# RamyunActionBoard.net
KiCad netlist of a schematic drawn in EAGLE
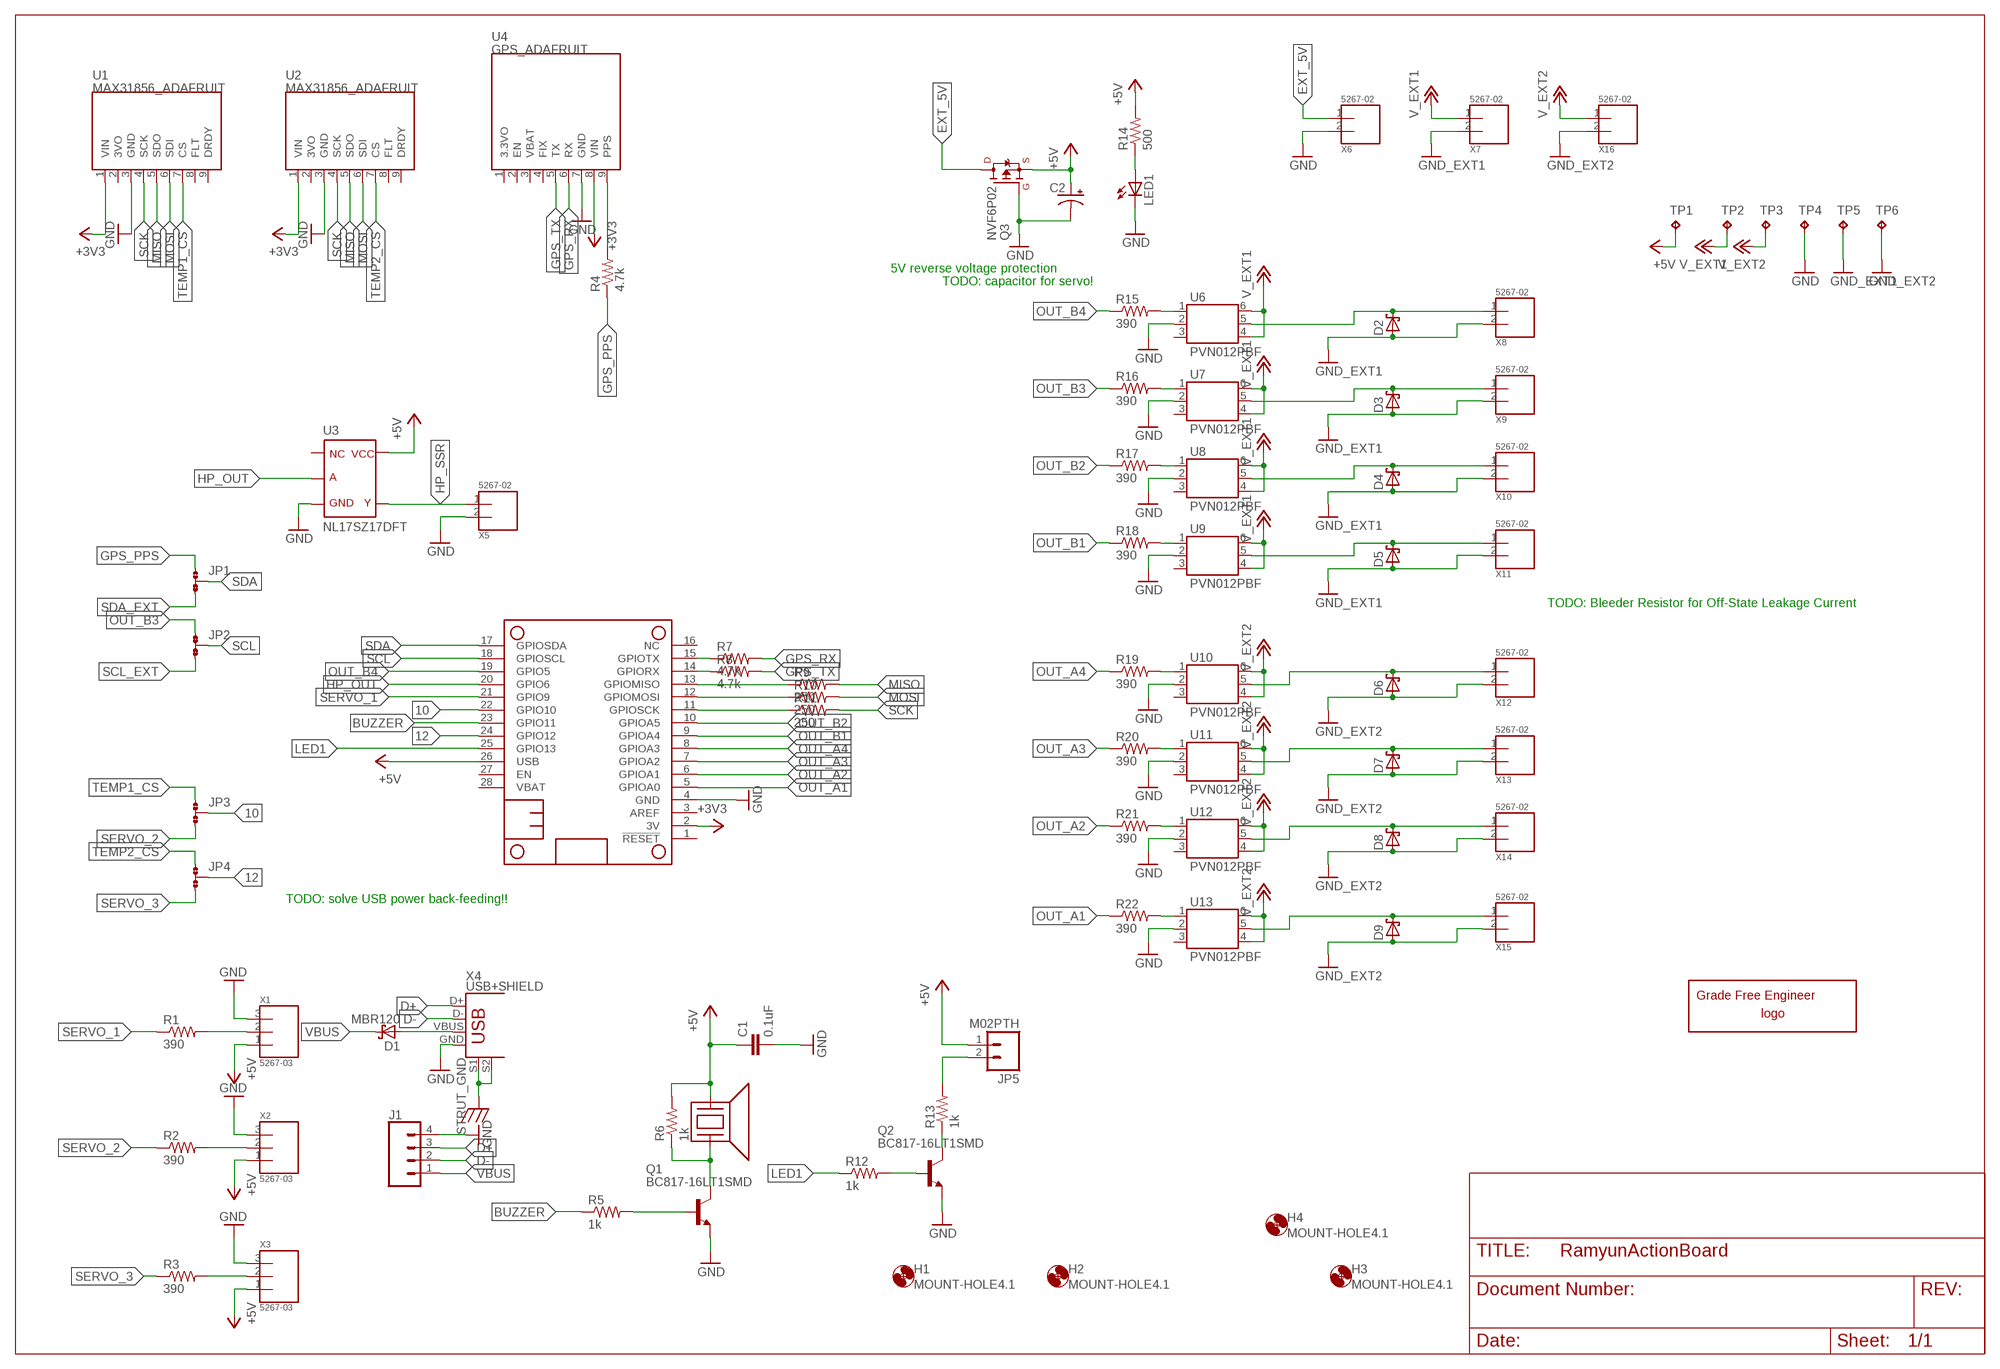
[diagram p0: schematic, sheet 1]

(export (version "E")
  (design (tool "Eeschema 10.0.6"))
  (components
    (comp (ref "C1")
      (value "0.1uF")
      (footprint "eagle-import:C0603(1608)_HANDSOLDER")
      (libsource (lib "eagle-import") (part "C0603(1608)_HAND"))
    )
    (comp (ref "C2")
      (value "CPOL-USE3.5-8")
      (footprint "eagle-import:E3,5-8")
      (libsource (lib "eagle-import") (part "CPOL-USE3.5-8"))
    )
    (comp (ref "D1")
      (value "MBR120")
      (footprint "eagle-import:SOD-123")
      (libsource (lib "eagle-import") (part "MBR120"))
    )
    (comp (ref "D2")
      (value "MBR5200VPTR-E1_V")
      (footprint "eagle-import:DO-27-VERTICAL")
      (libsource (lib "eagle-import") (part "MBR5200VPTR-E1_V"))
    )
    (comp (ref "D3")
      (value "MBR5200VPTR-E1_V")
      (footprint "eagle-import:DO-27-VERTICAL")
      (libsource (lib "eagle-import") (part "MBR5200VPTR-E1_V"))
    )
    (comp (ref "D4")
      (value "MBR5200VPTR-E1_V")
      (footprint "eagle-import:DO-27-VERTICAL")
      (libsource (lib "eagle-import") (part "MBR5200VPTR-E1_V"))
    )
    (comp (ref "D5")
      (value "MBR5200VPTR-E1_V")
      (footprint "eagle-import:DO-27-VERTICAL")
      (libsource (lib "eagle-import") (part "MBR5200VPTR-E1_V"))
    )
    (comp (ref "D6")
      (value "MBR5200VPTR-E1_V")
      (footprint "eagle-import:DO-27-VERTICAL")
      (libsource (lib "eagle-import") (part "MBR5200VPTR-E1_V"))
    )
    (comp (ref "D7")
      (value "MBR5200VPTR-E1_V")
      (footprint "eagle-import:DO-27-VERTICAL")
      (libsource (lib "eagle-import") (part "MBR5200VPTR-E1_V"))
    )
    (comp (ref "D8")
      (value "MBR5200VPTR-E1_V")
      (footprint "eagle-import:DO-27-VERTICAL")
      (libsource (lib "eagle-import") (part "MBR5200VPTR-E1_V"))
    )
    (comp (ref "D9")
      (value "MBR5200VPTR-E1_V")
      (footprint "eagle-import:DO-27-VERTICAL")
      (libsource (lib "eagle-import") (part "MBR5200VPTR-E1_V"))
    )
    (comp (ref "H1")
      (value "MOUNT-HOLE4.1")
      (footprint "eagle-import:4,1")
      (libsource (lib "eagle-import") (part "MOUNT-HOLE4.1"))
    )
    (comp (ref "H2")
      (value "MOUNT-HOLE4.1")
      (footprint "eagle-import:4,1")
      (libsource (lib "eagle-import") (part "MOUNT-HOLE4.1"))
    )
    (comp (ref "H3")
      (value "MOUNT-HOLE4.1")
      (footprint "eagle-import:4,1")
      (libsource (lib "eagle-import") (part "MOUNT-HOLE4.1"))
    )
    (comp (ref "H4")
      (value "MOUNT-HOLE4.1")
      (footprint "eagle-import:4,1")
      (libsource (lib "eagle-import") (part "MOUNT-HOLE4.1"))
    )
    (comp (ref "J1")
      (value "CONN_04")
      (footprint "eagle-import:1X04")
      (libsource (lib "eagle-import") (part "CONN_04"))
    )
    (comp (ref "JP1")
      (value "JP2")
      (footprint "eagle-import:JP2SMD0603")
      (libsource (lib "eagle-import") (part "JP2"))
    )
    (comp (ref "JP2")
      (value "JP2")
      (footprint "eagle-import:JP2SMD0603")
      (libsource (lib "eagle-import") (part "JP2"))
    )
    (comp (ref "JP3")
      (value "JP2")
      (footprint "eagle-import:JP2SMD0603")
      (libsource (lib "eagle-import") (part "JP2"))
    )
    (comp (ref "JP4")
      (value "JP2")
      (footprint "eagle-import:JP2SMD0603")
      (libsource (lib "eagle-import") (part "JP2"))
    )
    (comp (ref "JP5")
      (value "M02PTH")
      (footprint "eagle-import:1X02")
      (libsource (lib "eagle-import") (part "M02PTH"))
    )
    (comp (ref "LED1")
      (value "LED3MM")
      (footprint "eagle-import:LED3MM")
      (libsource (lib "eagle-import") (part "LED3MM"))
    )
    (comp (ref "LOGO1")
      (value "GRADEFREELOGO-20")
      (footprint "eagle-import:GRADEFREELOGO-20")
      (libsource (lib "eagle-import") (part "GRADEFREELOGO-20"))
    )
    (comp (ref "MS1")
      (value "FEATHERWING_NODIM")
      (footprint "eagle-import:FEATHERWING_DIM")
      (libsource (lib "eagle-import") (part "FEATHERWING_NODIM"))
    )
    (comp (ref "Q1")
      (value "BC817-16LT1SMD")
      (footprint "eagle-import:SOT23-BEC")
      (libsource (lib "eagle-import") (part "BC817SMD-16LT1"))
    )
    (comp (ref "Q2")
      (value "BC817-16LT1SMD")
      (footprint "eagle-import:SOT23-BEC")
      (libsource (lib "eagle-import") (part "BC817SMD-16LT1"))
    )
    (comp (ref "Q3")
      (value "NVF6P02")
      (footprint "eagle-import:SOT223")
      (libsource (lib "eagle-import") (part "NVF6P02"))
    )
    (comp (ref "R1")
      (value "390")
      (footprint "eagle-import:R0603(1608)_HANDSOLDER")
      (libsource (lib "eagle-import") (part "R0603(1608)_HAND"))
    )
    (comp (ref "R2")
      (value "390")
      (footprint "eagle-import:R0603(1608)_HANDSOLDER")
      (libsource (lib "eagle-import") (part "R0603(1608)_HAND"))
    )
    (comp (ref "R3")
      (value "390")
      (footprint "eagle-import:R0603(1608)_HANDSOLDER")
      (libsource (lib "eagle-import") (part "R0603(1608)_HAND"))
    )
    (comp (ref "R4")
      (value "4.7k")
      (footprint "eagle-import:R0603(1608)_HANDSOLDER")
      (libsource (lib "eagle-import") (part "R0603(1608)_HAND"))
    )
    (comp (ref "R5")
      (value "1k")
      (footprint "eagle-import:R0603(1608)_HANDSOLDER")
      (libsource (lib "eagle-import") (part "R0603(1608)_HAND"))
    )
    (comp (ref "R6")
      (value "1k")
      (footprint "eagle-import:R0603(1608)_HANDSOLDER")
      (libsource (lib "eagle-import") (part "R0603(1608)_HAND"))
    )
    (comp (ref "R7")
      (value "4.7k")
      (footprint "eagle-import:R0603(1608)_HANDSOLDER")
      (libsource (lib "eagle-import") (part "R0603(1608)_HAND"))
    )
    (comp (ref "R8")
      (value "4.7k")
      (footprint "eagle-import:R0603(1608)_HANDSOLDER")
      (libsource (lib "eagle-import") (part "R0603(1608)_HAND"))
    )
    (comp (ref "R9")
      (value "250")
      (footprint "eagle-import:R0603(1608)_HANDSOLDER")
      (libsource (lib "eagle-import") (part "R0603(1608)_HAND"))
    )
    (comp (ref "R10")
      (value "250")
      (footprint "eagle-import:R0603(1608)_HANDSOLDER")
      (libsource (lib "eagle-import") (part "R0603(1608)_HAND"))
    )
    (comp (ref "R11")
      (value "250")
      (footprint "eagle-import:R0603(1608)_HANDSOLDER")
      (libsource (lib "eagle-import") (part "R0603(1608)_HAND"))
    )
    (comp (ref "R12")
      (value "1k")
      (footprint "eagle-import:R0603(1608)_HANDSOLDER")
      (libsource (lib "eagle-import") (part "R0603(1608)_HAND"))
    )
    (comp (ref "R13")
      (value "1k")
      (footprint "eagle-import:R0603(1608)_HANDSOLDER")
      (libsource (lib "eagle-import") (part "R0603(1608)_HAND"))
    )
    (comp (ref "R14")
      (value "500")
      (footprint "eagle-import:R0603(1608)_HANDSOLDER")
      (libsource (lib "eagle-import") (part "R0603(1608)_HAND"))
    )
    (comp (ref "R15")
      (value "390")
      (footprint "eagle-import:R0603(1608)_HANDSOLDER")
      (libsource (lib "eagle-import") (part "R0603(1608)_HAND"))
    )
    (comp (ref "R16")
      (value "390")
      (footprint "eagle-import:R0603(1608)_HANDSOLDER")
      (libsource (lib "eagle-import") (part "R0603(1608)_HAND"))
    )
    (comp (ref "R17")
      (value "390")
      (footprint "eagle-import:R0603(1608)_HANDSOLDER")
      (libsource (lib "eagle-import") (part "R0603(1608)_HAND"))
    )
    (comp (ref "R18")
      (value "390")
      (footprint "eagle-import:R0603(1608)_HANDSOLDER")
      (libsource (lib "eagle-import") (part "R0603(1608)_HAND"))
    )
    (comp (ref "R19")
      (value "390")
      (footprint "eagle-import:R0603(1608)_HANDSOLDER")
      (libsource (lib "eagle-import") (part "R0603(1608)_HAND"))
    )
    (comp (ref "R20")
      (value "390")
      (footprint "eagle-import:R0603(1608)_HANDSOLDER")
      (libsource (lib "eagle-import") (part "R0603(1608)_HAND"))
    )
    (comp (ref "R21")
      (value "390")
      (footprint "eagle-import:R0603(1608)_HANDSOLDER")
      (libsource (lib "eagle-import") (part "R0603(1608)_HAND"))
    )
    (comp (ref "R22")
      (value "390")
      (footprint "eagle-import:R0603(1608)_HANDSOLDER")
      (libsource (lib "eagle-import") (part "R0603(1608)_HAND"))
    )
    (comp (ref "TP1")
      (value "TP-5010")
      (footprint "eagle-import:TP-5010")
      (libsource (lib "eagle-import") (part "TP-5010"))
    )
    (comp (ref "TP2")
      (value "TP-5010")
      (footprint "eagle-import:TP-5010")
      (libsource (lib "eagle-import") (part "TP-5010"))
    )
    (comp (ref "TP3")
      (value "TP-5010")
      (footprint "eagle-import:TP-5010")
      (libsource (lib "eagle-import") (part "TP-5010"))
    )
    (comp (ref "TP4")
      (value "TP-5010")
      (footprint "eagle-import:TP-5010")
      (libsource (lib "eagle-import") (part "TP-5010"))
    )
    (comp (ref "TP5")
      (value "TP-5010")
      (footprint "eagle-import:TP-5010")
      (libsource (lib "eagle-import") (part "TP-5010"))
    )
    (comp (ref "TP6")
      (value "TP-5010")
      (footprint "eagle-import:TP-5010")
      (libsource (lib "eagle-import") (part "TP-5010"))
    )
    (comp (ref "U1")
      (value "MAX31856_ADAFRUIT")
      (footprint "eagle-import:MAX31856_ADAFRUIT")
      (libsource (lib "eagle-import") (part "MAX31856_ADAFRUIT"))
    )
    (comp (ref "U2")
      (value "MAX31856_ADAFRUIT")
      (footprint "eagle-import:MAX31856_ADAFRUIT")
      (libsource (lib "eagle-import") (part "MAX31856_ADAFRUIT"))
    )
    (comp (ref "U3")
      (value "NL17SZ17DFT")
      (footprint "eagle-import:SOT-353")
      (libsource (lib "eagle-import") (part "NL17SZ17DFT"))
    )
    (comp (ref "U4")
      (value "GPS_ADAFRUIT")
      (footprint "eagle-import:GPS_ADAFRUIT")
      (libsource (lib "eagle-import") (part "GPS_ADAFRUIT"))
    )
    (comp (ref "U5")
      (value "BUZZER")
      (footprint "eagle-import:PS1240")
      (libsource (lib "eagle-import") (part "BUZZER"))
    )
    (comp (ref "U6")
      (value "PVN012PBF")
      (footprint "eagle-import:DIL06")
      (libsource (lib "eagle-import") (part "PVN012PBF"))
    )
    (comp (ref "U7")
      (value "PVN012PBF")
      (footprint "eagle-import:DIL06")
      (libsource (lib "eagle-import") (part "PVN012PBF"))
    )
    (comp (ref "U8")
      (value "PVN012PBF")
      (footprint "eagle-import:DIL06")
      (libsource (lib "eagle-import") (part "PVN012PBF"))
    )
    (comp (ref "U9")
      (value "PVN012PBF")
      (footprint "eagle-import:DIL06")
      (libsource (lib "eagle-import") (part "PVN012PBF"))
    )
    (comp (ref "U10")
      (value "PVN012PBF")
      (footprint "eagle-import:DIL06")
      (libsource (lib "eagle-import") (part "PVN012PBF"))
    )
    (comp (ref "U11")
      (value "PVN012PBF")
      (footprint "eagle-import:DIL06")
      (libsource (lib "eagle-import") (part "PVN012PBF"))
    )
    (comp (ref "U12")
      (value "PVN012PBF")
      (footprint "eagle-import:DIL06")
      (libsource (lib "eagle-import") (part "PVN012PBF"))
    )
    (comp (ref "U13")
      (value "PVN012PBF")
      (footprint "eagle-import:DIL06")
      (libsource (lib "eagle-import") (part "PVN012PBF"))
    )
    (comp (ref "X1")
      (value "5267-03")
      (footprint "eagle-import:5267-03")
      (libsource (lib "eagle-import") (part "5267-03"))
    )
    (comp (ref "X2")
      (value "5267-03")
      (footprint "eagle-import:5267-03")
      (libsource (lib "eagle-import") (part "5267-03"))
    )
    (comp (ref "X3")
      (value "5267-03")
      (footprint "eagle-import:5267-03")
      (libsource (lib "eagle-import") (part "5267-03"))
    )
    (comp (ref "X4")
      (value "USB+SHIELD")
      (footprint "eagle-import:USB-B-PTH")
      (libsource (lib "eagle-import") (part "USB+SHIELD"))
    )
    (comp (ref "X5")
      (value "5267-02")
      (footprint "eagle-import:5267-02")
      (libsource (lib "eagle-import") (part "5267-02"))
    )
    (comp (ref "X6")
      (value "5267-02")
      (footprint "eagle-import:5267-02")
      (libsource (lib "eagle-import") (part "5267-02"))
    )
    (comp (ref "X7")
      (value "5267-02")
      (footprint "eagle-import:5267-02")
      (libsource (lib "eagle-import") (part "5267-02"))
    )
    (comp (ref "X8")
      (value "5267-02")
      (footprint "eagle-import:5267-02")
      (libsource (lib "eagle-import") (part "5267-02"))
    )
    (comp (ref "X9")
      (value "5267-02")
      (footprint "eagle-import:5267-02")
      (libsource (lib "eagle-import") (part "5267-02"))
    )
    (comp (ref "X10")
      (value "5267-02")
      (footprint "eagle-import:5267-02")
      (libsource (lib "eagle-import") (part "5267-02"))
    )
    (comp (ref "X11")
      (value "5267-02")
      (footprint "eagle-import:5267-02")
      (libsource (lib "eagle-import") (part "5267-02"))
    )
    (comp (ref "X12")
      (value "5267-02")
      (footprint "eagle-import:5267-02")
      (libsource (lib "eagle-import") (part "5267-02"))
    )
    (comp (ref "X13")
      (value "5267-02")
      (footprint "eagle-import:5267-02")
      (libsource (lib "eagle-import") (part "5267-02"))
    )
    (comp (ref "X14")
      (value "5267-02")
      (footprint "eagle-import:5267-02")
      (libsource (lib "eagle-import") (part "5267-02"))
    )
    (comp (ref "X15")
      (value "5267-02")
      (footprint "eagle-import:5267-02")
      (libsource (lib "eagle-import") (part "5267-02"))
    )
    (comp (ref "X16")
      (value "5267-02")
      (footprint "eagle-import:5267-02")
      (libsource (lib "eagle-import") (part "5267-02"))
    )
  )
  (nets
    (net (code "1") (name "+3V3") (class "Default")
      (node (ref "MS1") (pin "2") (pinfunction "3V_2") (pintype "power_in"))
      (node (ref "U1") (pin "1") (pinfunction "VIN_1") (pintype "bidirectional"))
      (node (ref "U2") (pin "1") (pinfunction "VIN_1") (pintype "bidirectional"))
      (node (ref "U4") (pin "8") (pinfunction "VIN_8") (pintype "bidirectional"))
    )
    (net (code "2") (name "+5V") (class "Default")
      (node (ref "C1") (pin "1") (pinfunction "1_1") (pintype "passive"))
      (node (ref "C2") (pin "+") (pinfunction "+_+") (pintype "passive"))
      (node (ref "JP5") (pin "1") (pinfunction "1_1") (pintype "passive"))
      (node (ref "MS1") (pin "26") (pinfunction "USB_26") (pintype "power_in"))
      (node (ref "Q3") (pin "3") (pinfunction "S_3") (pintype "passive"))
      (node (ref "R14") (pin "2") (pinfunction "2_2") (pintype "passive"))
      (node (ref "R6") (pin "2") (pinfunction "2_2") (pintype "passive"))
      (node (ref "TP1") (pin "TP") (pinfunction "TP_TP") (pintype "input"))
      (node (ref "U3") (pin "5") (pinfunction "P$5_5") (pintype "power_in"))
      (node (ref "U5") (pin "1") (pinfunction "P$1_1") (pintype "bidirectional"))
      (node (ref "X1") (pin "1") (pinfunction "1_1") (pintype "bidirectional"))
      (node (ref "X2") (pin "1") (pinfunction "1_1") (pintype "bidirectional"))
      (node (ref "X3") (pin "1") (pinfunction "1_1") (pintype "bidirectional"))
    )
    (net (code "3") (name "/VBAT") (class "Default")
      (node (ref "MS1") (pin "28") (pinfunction "VBAT_28") (pintype "power_in"))
    )
    (net (code "4") (name "10") (class "Default")
      (node (ref "JP3") (pin "2") (pinfunction "2_2") (pintype "passive"))
      (node (ref "MS1") (pin "22") (pinfunction "GPIO10_22") (pintype "bidirectional"))
    )
    (net (code "5") (name "12") (class "Default")
      (node (ref "JP4") (pin "2") (pinfunction "2_2") (pintype "passive"))
      (node (ref "MS1") (pin "24") (pinfunction "GPIO12_24") (pintype "bidirectional"))
    )
    (net (code "6") (name "BUZZER") (class "Default")
      (node (ref "MS1") (pin "23") (pinfunction "GPIO11_23") (pintype "bidirectional"))
      (node (ref "R5") (pin "1") (pinfunction "1_1") (pintype "passive"))
    )
    (net (code "7") (name "D+") (class "Default")
      (node (ref "J1") (pin "3") (pinfunction "3_3") (pintype "passive"))
      (node (ref "X4") (pin "D+") (pinfunction "D+_D+") (pintype "bidirectional"))
    )
    (net (code "8") (name "D-") (class "Default")
      (node (ref "J1") (pin "2") (pinfunction "2_2") (pintype "passive"))
      (node (ref "X4") (pin "D-") (pinfunction "D-_D-") (pintype "bidirectional"))
    )
    (net (code "9") (name "EXT_5V") (class "Default")
      (node (ref "Q3") (pin "2") (pinfunction "D_2") (pintype "passive"))
      (node (ref "Q3") (pin "4") (pinfunction "D_4") (pintype "passive"))
      (node (ref "X6") (pin "1") (pinfunction "1_1") (pintype "bidirectional"))
    )
    (net (code "10") (name "GND") (class "Default")
      (node (ref "C1") (pin "2") (pinfunction "2_2") (pintype "passive"))
      (node (ref "C2") (pin "-") (pinfunction "-_-") (pintype "passive"))
      (node (ref "J1") (pin "4") (pinfunction "4_4") (pintype "passive"))
      (node (ref "LED1") (pin "K") (pinfunction "C_K") (pintype "passive"))
      (node (ref "MS1") (pin "4") (pinfunction "GND_4") (pintype "power_in"))
      (node (ref "Q1") (pin "E") (pinfunction "E_E") (pintype "passive"))
      (node (ref "Q2") (pin "E") (pinfunction "E_E") (pintype "passive"))
      (node (ref "Q3") (pin "1") (pinfunction "G_1") (pintype "passive"))
      (node (ref "TP4") (pin "TP") (pinfunction "TP_TP") (pintype "input"))
      (node (ref "U1") (pin "3") (pinfunction "GND_3") (pintype "bidirectional"))
      (node (ref "U10") (pin "2") (pinfunction "2_2") (pintype "passive"))
      (node (ref "U11") (pin "2") (pinfunction "2_2") (pintype "passive"))
      (node (ref "U12") (pin "2") (pinfunction "2_2") (pintype "passive"))
      (node (ref "U13") (pin "2") (pinfunction "2_2") (pintype "passive"))
      (node (ref "U2") (pin "3") (pinfunction "GND_3") (pintype "bidirectional"))
      (node (ref "U3") (pin "3") (pinfunction "P$3_3") (pintype "power_in"))
      (node (ref "U4") (pin "7") (pinfunction "GND_7") (pintype "bidirectional"))
      (node (ref "U6") (pin "2") (pinfunction "2_2") (pintype "passive"))
      (node (ref "U7") (pin "2") (pinfunction "2_2") (pintype "passive"))
      (node (ref "U8") (pin "2") (pinfunction "2_2") (pintype "passive"))
      (node (ref "U9") (pin "2") (pinfunction "2_2") (pintype "passive"))
      (node (ref "X1") (pin "3") (pinfunction "3_3") (pintype "bidirectional"))
      (node (ref "X2") (pin "3") (pinfunction "3_3") (pintype "bidirectional"))
      (node (ref "X3") (pin "3") (pinfunction "3_3") (pintype "bidirectional"))
      (node (ref "X4") (pin "GND") (pinfunction "GND_GND") (pintype "bidirectional"))
      (node (ref "X5") (pin "2") (pinfunction "2_2") (pintype "bidirectional"))
      (node (ref "X6") (pin "2") (pinfunction "2_2") (pintype "bidirectional"))
    )
    (net (code "11") (name "GND_EXT1") (class "Default")
      (node (ref "D2") (pin "A") (pinfunction "A_A") (pintype "passive"))
      (node (ref "D3") (pin "A") (pinfunction "A_A") (pintype "passive"))
      (node (ref "D4") (pin "A") (pinfunction "A_A") (pintype "passive"))
      (node (ref "D5") (pin "A") (pinfunction "A_A") (pintype "passive"))
      (node (ref "TP5") (pin "TP") (pinfunction "TP_TP") (pintype "input"))
      (node (ref "X10") (pin "2") (pinfunction "2_2") (pintype "bidirectional"))
      (node (ref "X11") (pin "2") (pinfunction "2_2") (pintype "bidirectional"))
      (node (ref "X7") (pin "2") (pinfunction "2_2") (pintype "bidirectional"))
      (node (ref "X8") (pin "2") (pinfunction "2_2") (pintype "bidirectional"))
      (node (ref "X9") (pin "2") (pinfunction "2_2") (pintype "bidirectional"))
    )
    (net (code "12") (name "GND_EXT2") (class "Default")
      (node (ref "D6") (pin "A") (pinfunction "A_A") (pintype "passive"))
      (node (ref "D7") (pin "A") (pinfunction "A_A") (pintype "passive"))
      (node (ref "D8") (pin "A") (pinfunction "A_A") (pintype "passive"))
      (node (ref "D9") (pin "A") (pinfunction "A_A") (pintype "passive"))
      (node (ref "TP6") (pin "TP") (pinfunction "TP_TP") (pintype "input"))
      (node (ref "X12") (pin "2") (pinfunction "2_2") (pintype "bidirectional"))
      (node (ref "X13") (pin "2") (pinfunction "2_2") (pintype "bidirectional"))
      (node (ref "X14") (pin "2") (pinfunction "2_2") (pintype "bidirectional"))
      (node (ref "X15") (pin "2") (pinfunction "2_2") (pintype "bidirectional"))
      (node (ref "X16") (pin "2") (pinfunction "2_2") (pintype "bidirectional"))
    )
    (net (code "13") (name "GPS_PPS") (class "Default")
      (node (ref "JP1") (pin "1") (pinfunction "1_1") (pintype "passive"))
      (node (ref "R4") (pin "1") (pinfunction "1_1") (pintype "passive"))
    )
    (net (code "14") (name "GPS_RX") (class "Default")
      (node (ref "R7") (pin "2") (pinfunction "2_2") (pintype "passive"))
      (node (ref "U4") (pin "6") (pinfunction "RX_6") (pintype "bidirectional"))
    )
    (net (code "15") (name "GPS_TX") (class "Default")
      (node (ref "R8") (pin "2") (pinfunction "2_2") (pintype "passive"))
      (node (ref "U4") (pin "5") (pinfunction "TX_5") (pintype "bidirectional"))
    )
    (net (code "16") (name "HP_OUT") (class "Default")
      (node (ref "MS1") (pin "20") (pinfunction "GPIO6_20") (pintype "bidirectional"))
      (node (ref "U3") (pin "2") (pinfunction "P$2_2") (pintype "input"))
    )
    (net (code "17") (name "HP_SSR") (class "Default")
      (node (ref "U3") (pin "4") (pinfunction "P$4_4") (pintype "output"))
      (node (ref "X5") (pin "1") (pinfunction "1_1") (pintype "bidirectional"))
    )
    (net (code "18") (name "LED1") (class "Default")
      (node (ref "MS1") (pin "25") (pinfunction "GPIO13_25") (pintype "bidirectional"))
      (node (ref "R12") (pin "1") (pinfunction "1_1") (pintype "passive"))
    )
    (net (code "19") (name "MISO") (class "Default")
      (node (ref "R9") (pin "2") (pinfunction "2_2") (pintype "passive"))
      (node (ref "U1") (pin "5") (pinfunction "SDO_5") (pintype "bidirectional"))
      (node (ref "U2") (pin "5") (pinfunction "SDO_5") (pintype "bidirectional"))
    )
    (net (code "20") (name "MOSI") (class "Default")
      (node (ref "R10") (pin "2") (pinfunction "2_2") (pintype "passive"))
      (node (ref "U1") (pin "6") (pinfunction "SDI_6") (pintype "bidirectional"))
      (node (ref "U2") (pin "6") (pinfunction "SDI_6") (pintype "bidirectional"))
    )
    (net (code "21") (name "Net-(D1-PadA)") (class "Default")
      (node (ref "D1") (pin "A") (pinfunction "A_A") (pintype "passive"))
      (node (ref "X4") (pin "VBUS") (pinfunction "VBUS_VBUS") (pintype "bidirectional"))
    )
    (net (code "22") (name "Net-(D2-PadC)") (class "Default")
      (node (ref "D2") (pin "C") (pinfunction "C_C") (pintype "passive"))
      (node (ref "U6") (pin "5") (pinfunction "5_5") (pintype "passive"))
      (node (ref "X8") (pin "1") (pinfunction "1_1") (pintype "bidirectional"))
    )
    (net (code "23") (name "Net-(D3-PadC)") (class "Default")
      (node (ref "D3") (pin "C") (pinfunction "C_C") (pintype "passive"))
      (node (ref "U7") (pin "5") (pinfunction "5_5") (pintype "passive"))
      (node (ref "X9") (pin "1") (pinfunction "1_1") (pintype "bidirectional"))
    )
    (net (code "24") (name "Net-(D4-PadC)") (class "Default")
      (node (ref "D4") (pin "C") (pinfunction "C_C") (pintype "passive"))
      (node (ref "U8") (pin "5") (pinfunction "5_5") (pintype "passive"))
      (node (ref "X10") (pin "1") (pinfunction "1_1") (pintype "bidirectional"))
    )
    (net (code "25") (name "Net-(D5-PadC)") (class "Default")
      (node (ref "D5") (pin "C") (pinfunction "C_C") (pintype "passive"))
      (node (ref "U9") (pin "5") (pinfunction "5_5") (pintype "passive"))
      (node (ref "X11") (pin "1") (pinfunction "1_1") (pintype "bidirectional"))
    )
    (net (code "26") (name "Net-(D6-PadC)") (class "Default")
      (node (ref "D6") (pin "C") (pinfunction "C_C") (pintype "passive"))
      (node (ref "U10") (pin "5") (pinfunction "5_5") (pintype "passive"))
      (node (ref "X12") (pin "1") (pinfunction "1_1") (pintype "bidirectional"))
    )
    (net (code "27") (name "Net-(D7-PadC)") (class "Default")
      (node (ref "D7") (pin "C") (pinfunction "C_C") (pintype "passive"))
      (node (ref "U11") (pin "5") (pinfunction "5_5") (pintype "passive"))
      (node (ref "X13") (pin "1") (pinfunction "1_1") (pintype "bidirectional"))
    )
    (net (code "28") (name "Net-(D8-PadC)") (class "Default")
      (node (ref "D8") (pin "C") (pinfunction "C_C") (pintype "passive"))
      (node (ref "U12") (pin "5") (pinfunction "5_5") (pintype "passive"))
      (node (ref "X14") (pin "1") (pinfunction "1_1") (pintype "bidirectional"))
    )
    (net (code "29") (name "Net-(D9-PadC)") (class "Default")
      (node (ref "D9") (pin "C") (pinfunction "C_C") (pintype "passive"))
      (node (ref "U13") (pin "5") (pinfunction "5_5") (pintype "passive"))
      (node (ref "X15") (pin "1") (pinfunction "1_1") (pintype "bidirectional"))
    )
    (net (code "30") (name "Net-(JP5-Pad2)") (class "Default")
      (node (ref "JP5") (pin "2") (pinfunction "2_2") (pintype "passive"))
      (node (ref "R13") (pin "2") (pinfunction "2_2") (pintype "passive"))
    )
    (net (code "31") (name "Net-(LED1-PadA)") (class "Default")
      (node (ref "LED1") (pin "A") (pinfunction "A_A") (pintype "passive"))
      (node (ref "R14") (pin "1") (pinfunction "1_1") (pintype "passive"))
    )
    (net (code "32") (name "Net-(MS1-GPIOMISO)") (class "Default")
      (node (ref "MS1") (pin "13") (pinfunction "GPIOMISO_13") (pintype "bidirectional"))
      (node (ref "R9") (pin "1") (pinfunction "1_1") (pintype "passive"))
    )
    (net (code "33") (name "Net-(MS1-GPIOMOSI)") (class "Default")
      (node (ref "MS1") (pin "12") (pinfunction "GPIOMOSI_12") (pintype "bidirectional"))
      (node (ref "R10") (pin "1") (pinfunction "1_1") (pintype "passive"))
    )
    (net (code "34") (name "Net-(MS1-GPIORX)") (class "Default")
      (node (ref "MS1") (pin "14") (pinfunction "GPIORX_14") (pintype "bidirectional"))
      (node (ref "R8") (pin "1") (pinfunction "1_1") (pintype "passive"))
    )
    (net (code "35") (name "Net-(MS1-GPIOSCK)") (class "Default")
      (node (ref "MS1") (pin "11") (pinfunction "GPIOSCK_11") (pintype "bidirectional"))
      (node (ref "R11") (pin "1") (pinfunction "1_1") (pintype "passive"))
    )
    (net (code "36") (name "Net-(MS1-GPIOTX)") (class "Default")
      (node (ref "MS1") (pin "15") (pinfunction "GPIOTX_15") (pintype "bidirectional"))
      (node (ref "R7") (pin "1") (pinfunction "1_1") (pintype "passive"))
    )
    (net (code "37") (name "Net-(Q1-PadB)") (class "Default")
      (node (ref "Q1") (pin "B") (pinfunction "B_B") (pintype "passive"))
      (node (ref "R5") (pin "2") (pinfunction "2_2") (pintype "passive"))
    )
    (net (code "38") (name "Net-(Q2-PadB)") (class "Default")
      (node (ref "Q2") (pin "B") (pinfunction "B_B") (pintype "passive"))
      (node (ref "R12") (pin "2") (pinfunction "2_2") (pintype "passive"))
    )
    (net (code "39") (name "Net-(Q2-PadC)") (class "Default")
      (node (ref "Q2") (pin "C") (pinfunction "C_C") (pintype "passive"))
      (node (ref "R13") (pin "1") (pinfunction "1_1") (pintype "passive"))
    )
    (net (code "40") (name "Net-(R1-Pad2)") (class "Default")
      (node (ref "R1") (pin "2") (pinfunction "2_2") (pintype "passive"))
      (node (ref "X1") (pin "2") (pinfunction "2_2") (pintype "bidirectional"))
    )
    (net (code "41") (name "Net-(R2-Pad2)") (class "Default")
      (node (ref "R2") (pin "2") (pinfunction "2_2") (pintype "passive"))
      (node (ref "X2") (pin "2") (pinfunction "2_2") (pintype "bidirectional"))
    )
    (net (code "42") (name "Net-(R3-Pad2)") (class "Default")
      (node (ref "R3") (pin "2") (pinfunction "2_2") (pintype "passive"))
      (node (ref "X3") (pin "2") (pinfunction "2_2") (pintype "bidirectional"))
    )
    (net (code "43") (name "Net-(R15-Pad2)") (class "Default")
      (node (ref "R15") (pin "2") (pinfunction "2_2") (pintype "passive"))
      (node (ref "U6") (pin "1") (pinfunction "1_1") (pintype "passive"))
    )
    (net (code "44") (name "Net-(R16-Pad2)") (class "Default")
      (node (ref "R16") (pin "2") (pinfunction "2_2") (pintype "passive"))
      (node (ref "U7") (pin "1") (pinfunction "1_1") (pintype "passive"))
    )
    (net (code "45") (name "Net-(R17-Pad2)") (class "Default")
      (node (ref "R17") (pin "2") (pinfunction "2_2") (pintype "passive"))
      (node (ref "U8") (pin "1") (pinfunction "1_1") (pintype "passive"))
    )
    (net (code "46") (name "Net-(R18-Pad2)") (class "Default")
      (node (ref "R18") (pin "2") (pinfunction "2_2") (pintype "passive"))
      (node (ref "U9") (pin "1") (pinfunction "1_1") (pintype "passive"))
    )
    (net (code "47") (name "Net-(R19-Pad2)") (class "Default")
      (node (ref "R19") (pin "2") (pinfunction "2_2") (pintype "passive"))
      (node (ref "U10") (pin "1") (pinfunction "1_1") (pintype "passive"))
    )
    (net (code "48") (name "Net-(R20-Pad2)") (class "Default")
      (node (ref "R20") (pin "2") (pinfunction "2_2") (pintype "passive"))
      (node (ref "U11") (pin "1") (pinfunction "1_1") (pintype "passive"))
    )
    (net (code "49") (name "Net-(R21-Pad2)") (class "Default")
      (node (ref "R21") (pin "2") (pinfunction "2_2") (pintype "passive"))
      (node (ref "U12") (pin "1") (pinfunction "1_1") (pintype "passive"))
    )
    (net (code "50") (name "Net-(R22-Pad2)") (class "Default")
      (node (ref "R22") (pin "2") (pinfunction "2_2") (pintype "passive"))
      (node (ref "U13") (pin "1") (pinfunction "1_1") (pintype "passive"))
    )
    (net (code "51") (name "Net-(U4-PPS)") (class "Default")
      (node (ref "R4") (pin "2") (pinfunction "2_2") (pintype "passive"))
      (node (ref "U4") (pin "9") (pinfunction "PPS_9") (pintype "bidirectional"))
    )
    (net (code "52") (name "Net-(U5-P$2)") (class "Default")
      (node (ref "Q1") (pin "C") (pinfunction "C_C") (pintype "passive"))
      (node (ref "R6") (pin "1") (pinfunction "1_1") (pintype "passive"))
      (node (ref "U5") (pin "2") (pinfunction "P$2_2") (pintype "bidirectional"))
    )
    (net (code "53") (name "OUT_A1") (class "Default")
      (node (ref "MS1") (pin "5") (pinfunction "GPIOA0_5") (pintype "bidirectional"))
      (node (ref "R22") (pin "1") (pinfunction "1_1") (pintype "passive"))
    )
    (net (code "54") (name "OUT_A2") (class "Default")
      (node (ref "MS1") (pin "6") (pinfunction "GPIOA1_6") (pintype "bidirectional"))
      (node (ref "R21") (pin "1") (pinfunction "1_1") (pintype "passive"))
    )
    (net (code "55") (name "OUT_A3") (class "Default")
      (node (ref "MS1") (pin "7") (pinfunction "GPIOA2_7") (pintype "bidirectional"))
      (node (ref "R20") (pin "1") (pinfunction "1_1") (pintype "passive"))
    )
    (net (code "56") (name "OUT_A4") (class "Default")
      (node (ref "MS1") (pin "8") (pinfunction "GPIOA3_8") (pintype "bidirectional"))
      (node (ref "R19") (pin "1") (pinfunction "1_1") (pintype "passive"))
    )
    (net (code "57") (name "OUT_B1") (class "Default")
      (node (ref "MS1") (pin "9") (pinfunction "GPIOA4_9") (pintype "bidirectional"))
      (node (ref "R18") (pin "1") (pinfunction "1_1") (pintype "passive"))
    )
    (net (code "58") (name "OUT_B2") (class "Default")
      (node (ref "MS1") (pin "10") (pinfunction "GPIOA5_10") (pintype "bidirectional"))
      (node (ref "R17") (pin "1") (pinfunction "1_1") (pintype "passive"))
    )
    (net (code "59") (name "OUT_B3") (class "Default")
      (node (ref "JP2") (pin "1") (pinfunction "1_1") (pintype "passive"))
      (node (ref "R16") (pin "1") (pinfunction "1_1") (pintype "passive"))
    )
    (net (code "60") (name "OUT_B4") (class "Default")
      (node (ref "MS1") (pin "19") (pinfunction "GPIO5_19") (pintype "bidirectional"))
      (node (ref "R15") (pin "1") (pinfunction "1_1") (pintype "passive"))
    )
    (net (code "61") (name "SCK") (class "Default")
      (node (ref "R11") (pin "2") (pinfunction "2_2") (pintype "passive"))
      (node (ref "U1") (pin "4") (pinfunction "SCK_4") (pintype "bidirectional"))
      (node (ref "U2") (pin "4") (pinfunction "SCK_4") (pintype "bidirectional"))
    )
    (net (code "62") (name "SCL") (class "Default")
      (node (ref "JP2") (pin "2") (pinfunction "2_2") (pintype "passive"))
      (node (ref "MS1") (pin "18") (pinfunction "GPIOSCL_18") (pintype "bidirectional"))
    )
    (net (code "63") (name "SCL_EXT") (class "Default")
      (node (ref "JP2") (pin "3") (pinfunction "3_3") (pintype "passive"))
    )
    (net (code "64") (name "SDA") (class "Default")
      (node (ref "JP1") (pin "2") (pinfunction "2_2") (pintype "passive"))
      (node (ref "MS1") (pin "17") (pinfunction "GPIOSDA_17") (pintype "bidirectional"))
    )
    (net (code "65") (name "SDA_EXT") (class "Default")
      (node (ref "JP1") (pin "3") (pinfunction "3_3") (pintype "passive"))
    )
    (net (code "66") (name "SERVO_1") (class "Default")
      (node (ref "MS1") (pin "21") (pinfunction "GPIO9_21") (pintype "bidirectional"))
      (node (ref "R1") (pin "1") (pinfunction "1_1") (pintype "passive"))
    )
    (net (code "67") (name "SERVO_2") (class "Default")
      (node (ref "JP3") (pin "3") (pinfunction "3_3") (pintype "passive"))
      (node (ref "R2") (pin "1") (pinfunction "1_1") (pintype "passive"))
    )
    (net (code "68") (name "SERVO_3") (class "Default")
      (node (ref "JP4") (pin "3") (pinfunction "3_3") (pintype "passive"))
      (node (ref "R3") (pin "1") (pinfunction "1_1") (pintype "passive"))
    )
    (net (code "69") (name "STRUT_GND") (class "Default")
      (node (ref "X4") (pin "S1") (pinfunction "S1_S1") (pintype "bidirectional"))
      (node (ref "X4") (pin "S2") (pinfunction "S2_S2") (pintype "bidirectional"))
    )
    (net (code "70") (name "TEMP1_CS") (class "Default")
      (node (ref "JP3") (pin "1") (pinfunction "1_1") (pintype "passive"))
      (node (ref "U1") (pin "7") (pinfunction "CS_7") (pintype "bidirectional"))
    )
    (net (code "71") (name "TEMP2_CS") (class "Default")
      (node (ref "JP4") (pin "1") (pinfunction "1_1") (pintype "passive"))
      (node (ref "U2") (pin "7") (pinfunction "CS_7") (pintype "bidirectional"))
    )
    (net (code "72") (name "VBUS") (class "Default")
      (node (ref "D1") (pin "C") (pinfunction "C_C") (pintype "passive"))
      (node (ref "J1") (pin "1") (pinfunction "1_1") (pintype "passive"))
    )
    (net (code "73") (name "V_EXT1") (class "Default")
      (node (ref "TP2") (pin "TP") (pinfunction "TP_TP") (pintype "input"))
      (node (ref "U6") (pin "4") (pinfunction "4_4") (pintype "passive"))
      (node (ref "U6") (pin "6") (pinfunction "6_6") (pintype "passive"))
      (node (ref "U7") (pin "4") (pinfunction "4_4") (pintype "passive"))
      (node (ref "U7") (pin "6") (pinfunction "6_6") (pintype "passive"))
      (node (ref "U8") (pin "4") (pinfunction "4_4") (pintype "passive"))
      (node (ref "U8") (pin "6") (pinfunction "6_6") (pintype "passive"))
      (node (ref "U9") (pin "4") (pinfunction "4_4") (pintype "passive"))
      (node (ref "U9") (pin "6") (pinfunction "6_6") (pintype "passive"))
      (node (ref "X7") (pin "1") (pinfunction "1_1") (pintype "bidirectional"))
    )
    (net (code "74") (name "V_EXT2") (class "Default")
      (node (ref "TP3") (pin "TP") (pinfunction "TP_TP") (pintype "input"))
      (node (ref "U10") (pin "4") (pinfunction "4_4") (pintype "passive"))
      (node (ref "U10") (pin "6") (pinfunction "6_6") (pintype "passive"))
      (node (ref "U11") (pin "4") (pinfunction "4_4") (pintype "passive"))
      (node (ref "U11") (pin "6") (pinfunction "6_6") (pintype "passive"))
      (node (ref "U12") (pin "4") (pinfunction "4_4") (pintype "passive"))
      (node (ref "U12") (pin "6") (pinfunction "6_6") (pintype "passive"))
      (node (ref "U13") (pin "4") (pinfunction "4_4") (pintype "passive"))
      (node (ref "U13") (pin "6") (pinfunction "6_6") (pintype "passive"))
      (node (ref "X16") (pin "1") (pinfunction "1_1") (pintype "bidirectional"))
    )
    (net (code "75") (name "unconnected-(MS1-AREF-Pad3)") (class "Default")
      (node (ref "MS1") (pin "3") (pinfunction "AREF_3") (pintype "passive"))
    )
    (net (code "76") (name "unconnected-(MS1-EN-Pad27)") (class "Default")
      (node (ref "MS1") (pin "27") (pinfunction "EN_27") (pintype "passive"))
    )
    (net (code "77") (name "unconnected-(MS1-NC-Pad16)") (class "Default")
      (node (ref "MS1") (pin "16") (pinfunction "NC_16") (pintype "passive"))
    )
    (net (code "78") (name "unconnected-(MS1-~{RESET}-Pad1)") (class "Default")
      (node (ref "MS1") (pin "1") (pinfunction "~{RESET}_1") (pintype "input"))
    )
    (net (code "79") (name "unconnected-(U1-3VO-Pad2)") (class "Default")
      (node (ref "U1") (pin "2") (pinfunction "3VO_2") (pintype "bidirectional"))
    )
    (net (code "80") (name "unconnected-(U1-DRDY-Pad9)") (class "Default")
      (node (ref "U1") (pin "9") (pinfunction "DRDY_9") (pintype "bidirectional"))
    )
    (net (code "81") (name "unconnected-(U1-FLT-Pad8)") (class "Default")
      (node (ref "U1") (pin "8") (pinfunction "FLT_8") (pintype "bidirectional"))
    )
    (net (code "82") (name "unconnected-(U2-3VO-Pad2)") (class "Default")
      (node (ref "U2") (pin "2") (pinfunction "3VO_2") (pintype "bidirectional"))
    )
    (net (code "83") (name "unconnected-(U2-DRDY-Pad9)") (class "Default")
      (node (ref "U2") (pin "9") (pinfunction "DRDY_9") (pintype "bidirectional"))
    )
    (net (code "84") (name "unconnected-(U2-FLT-Pad8)") (class "Default")
      (node (ref "U2") (pin "8") (pinfunction "FLT_8") (pintype "bidirectional"))
    )
    (net (code "85") (name "unconnected-(U3-P$1-Pad1)") (class "Default")
      (node (ref "U3") (pin "1") (pinfunction "P$1_1") (pintype "no_connect"))
    )
    (net (code "86") (name "unconnected-(U4-3.3VO-Pad1)") (class "Default")
      (node (ref "U4") (pin "1") (pinfunction "3.3VO_1") (pintype "bidirectional"))
    )
    (net (code "87") (name "unconnected-(U4-EN-Pad2)") (class "Default")
      (node (ref "U4") (pin "2") (pinfunction "EN_2") (pintype "bidirectional"))
    )
    (net (code "88") (name "unconnected-(U4-FIX-Pad4)") (class "Default")
      (node (ref "U4") (pin "4") (pinfunction "FIX_4") (pintype "bidirectional"))
    )
    (net (code "89") (name "unconnected-(U4-VBAT-Pad3)") (class "Default")
      (node (ref "U4") (pin "3") (pinfunction "VBAT_3") (pintype "bidirectional"))
    )
    (net (code "90") (name "unconnected-(U6-Pad3)") (class "Default")
      (node (ref "U6") (pin "3") (pinfunction "3_3") (pintype "passive"))
    )
    (net (code "91") (name "unconnected-(U7-Pad3)") (class "Default")
      (node (ref "U7") (pin "3") (pinfunction "3_3") (pintype "passive"))
    )
    (net (code "92") (name "unconnected-(U8-Pad3)") (class "Default")
      (node (ref "U8") (pin "3") (pinfunction "3_3") (pintype "passive"))
    )
    (net (code "93") (name "unconnected-(U9-Pad3)") (class "Default")
      (node (ref "U9") (pin "3") (pinfunction "3_3") (pintype "passive"))
    )
    (net (code "94") (name "unconnected-(U10-Pad3)") (class "Default")
      (node (ref "U10") (pin "3") (pinfunction "3_3") (pintype "passive"))
    )
    (net (code "95") (name "unconnected-(U11-Pad3)") (class "Default")
      (node (ref "U11") (pin "3") (pinfunction "3_3") (pintype "passive"))
    )
    (net (code "96") (name "unconnected-(U12-Pad3)") (class "Default")
      (node (ref "U12") (pin "3") (pinfunction "3_3") (pintype "passive"))
    )
    (net (code "97") (name "unconnected-(U13-Pad3)") (class "Default")
      (node (ref "U13") (pin "3") (pinfunction "3_3") (pintype "passive"))
    )
  )
)
